# PicoPrint-MOSFETs.net
KiCad netlist of a schematic drawn in Altium Designer
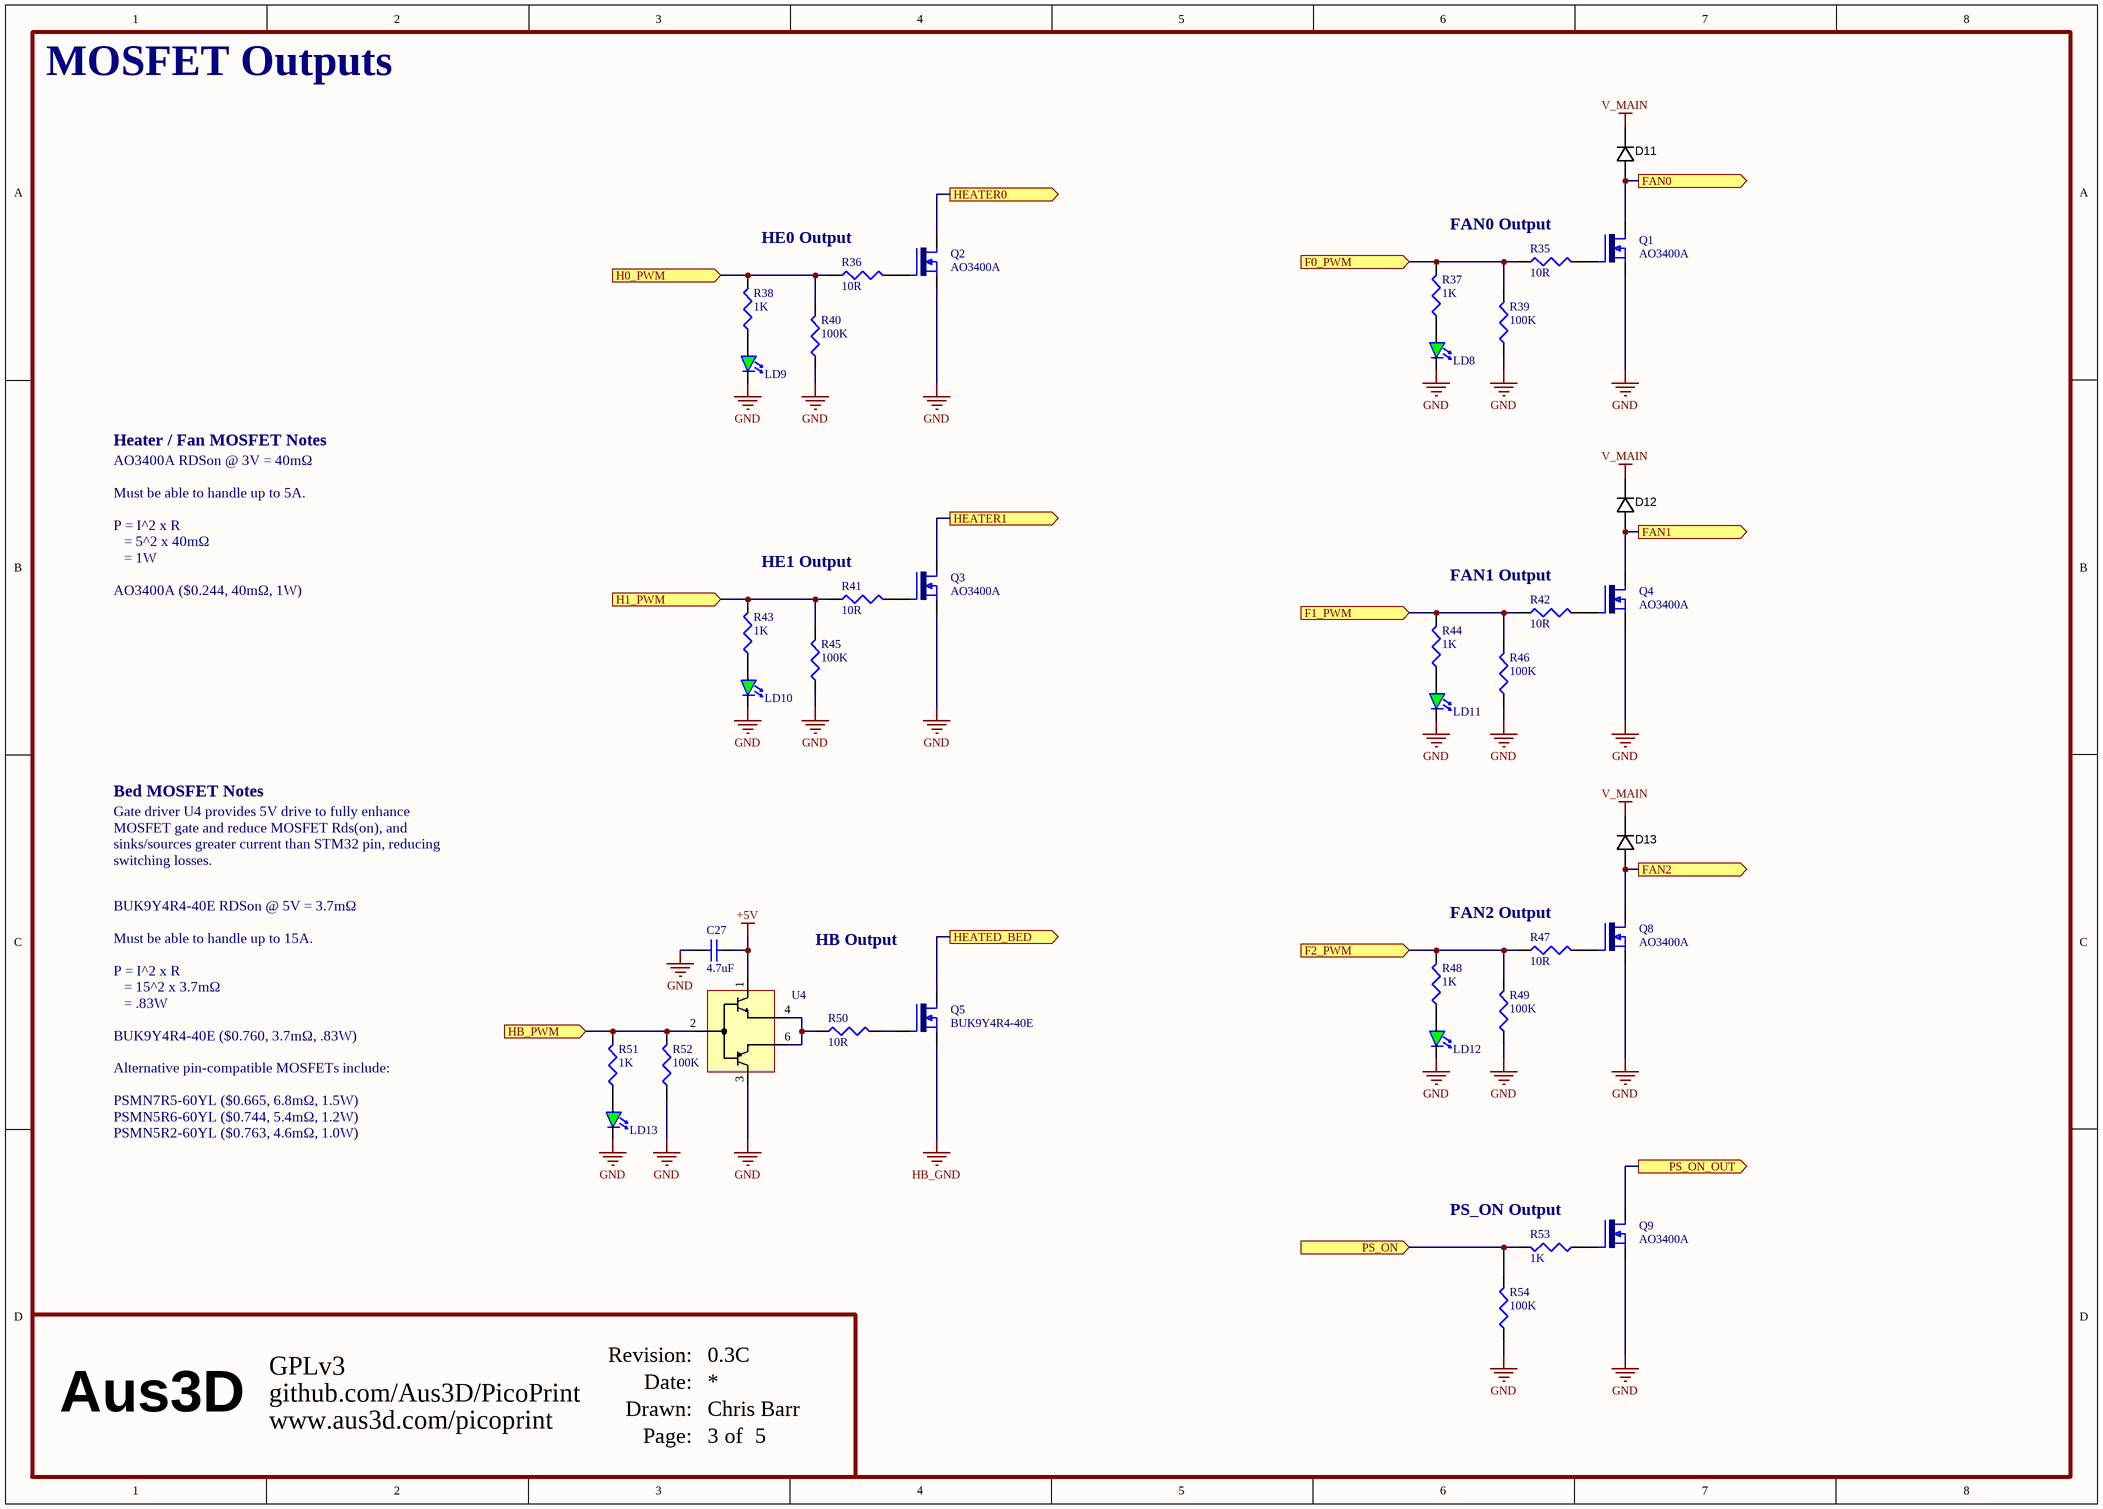
[diagram p0: PicoPrint-MOSFETs.SchDoc]

(export (version "E")
  (design (tool "Eeschema 10.0.6"))
  (components
    (comp (ref "C27")
      (value "4.7uF")
      (footprint "CAP 1005-0402")
      (description "Capacitor (SMD Ceramic)")
      (fields
        (field (name "VOLTAGE") "10V")
        (field (name "Comment") "CapC-0402-4.7uF-10V")
        (field (name "PUBLISHER") "Altium Limited")
      )
      (libsource (lib "picoprint_library") (part "CapC-0402-4.7uF-10V"))
    )
    (comp (ref "D11")
      (value "General 500mW 75V SOD323")
      (footprint "SOD323")
      (description "Diode (SMD)")
      (fields
        (field (name "MANUFACTURER") "Micro Commercial Co")
        (field (name "MANUFACTURER PART NUMBER") "1N4148WX-TP")
      )
      (libsource (lib "PBL - Diodes") (part "DIODE_75V_500mW"))
    )
    (comp (ref "D12")
      (value "General 500mW 75V SOD323")
      (footprint "SOD323")
      (description "Diode (SMD)")
      (fields
        (field (name "MANUFACTURER") "Micro Commercial Co")
        (field (name "MANUFACTURER PART NUMBER") "1N4148WX-TP")
      )
      (libsource (lib "PBL - Diodes") (part "DIODE_75V_500mW"))
    )
    (comp (ref "D13")
      (value "General 500mW 75V SOD323")
      (footprint "SOD323")
      (description "Diode (SMD)")
      (fields
        (field (name "MANUFACTURER") "Micro Commercial Co")
        (field (name "MANUFACTURER PART NUMBER") "1N4148WX-TP")
      )
      (libsource (lib "PBL - Diodes") (part "DIODE_75V_500mW"))
    )
    (comp (ref "LD8")
      (value "LED-0402")
      (footprint "LED 0402")
      (description "LED (SMD)")
      (libsource (lib "picoprint_library") (part "LEDG  0402"))
    )
    (comp (ref "LD9")
      (value "LED-0402")
      (footprint "LED 0402")
      (description "LED (SMD)")
      (libsource (lib "picoprint_library") (part "LEDG  0402"))
    )
    (comp (ref "LD10")
      (value "LED-0402")
      (footprint "LED 0402")
      (description "LED (SMD)")
      (libsource (lib "picoprint_library") (part "LEDG  0402"))
    )
    (comp (ref "LD11")
      (value "LED-0402")
      (footprint "LED 0402")
      (description "LED (SMD)")
      (libsource (lib "picoprint_library") (part "LEDG  0402"))
    )
    (comp (ref "LD12")
      (value "LED-0402")
      (footprint "LED 0402")
      (description "LED (SMD)")
      (libsource (lib "picoprint_library") (part "LEDG  0402"))
    )
    (comp (ref "LD13")
      (value "LED-0402")
      (footprint "LED 0402")
      (description "LED (SMD)")
      (libsource (lib "picoprint_library") (part "LEDG  0402"))
    )
    (comp (ref "Q1")
      (value "AO3400A")
      (footprint "SOT23-3 New")
      (description "N-CH MOSFET 30V 5.7A SOT23")
      (libsource (lib "picoprint_library") (part "MOSFET - AO3400A"))
    )
    (comp (ref "Q2")
      (value "AO3400A")
      (footprint "SOT23-3 New")
      (description "N-CH MOSFET 30V 5.7A SOT23")
      (libsource (lib "picoprint_library") (part "MOSFET - AO3400A"))
    )
    (comp (ref "Q3")
      (value "AO3400A")
      (footprint "SOT23-3 New")
      (description "N-CH MOSFET 30V 5.7A SOT23")
      (libsource (lib "picoprint_library") (part "MOSFET - AO3400A"))
    )
    (comp (ref "Q4")
      (value "AO3400A")
      (footprint "SOT23-3 New")
      (description "N-CH MOSFET 30V 5.7A SOT23")
      (libsource (lib "picoprint_library") (part "MOSFET - AO3400A"))
    )
    (comp (ref "Q5")
      (value "BUK9Y4R4-40E")
      (footprint "LFPACK")
      (description "N-CH MOSFET 40V 100A LFPAK")
      (libsource (lib "picoprint_library") (part "MOSFET - PSMN1R8-40YLC"))
    )
    (comp (ref "Q8")
      (value "AO3400A")
      (footprint "SOT23-3 New")
      (description "N-CH MOSFET 30V 5.7A SOT23")
      (libsource (lib "picoprint_library") (part "MOSFET - AO3400A"))
    )
    (comp (ref "Q9")
      (value "AO3400A")
      (footprint "SOT23-3 New")
      (description "N-CH MOSFET 30V 5.7A SOT23")
      (libsource (lib "picoprint_library") (part "MOSFET - AO3400A"))
    )
    (comp (ref "R35")
      (value "10R")
      (footprint "RESC1005X40N")
      (description "Resistor")
      (fields (field (name "Comment") "Res-0402-10R") (field (name "PUBLISHER") "Altium Limited"))
      (libsource (lib "picoprint_library") (part "Res-0402-10R"))
    )
    (comp (ref "R36")
      (value "10R")
      (footprint "RESC1005X40N")
      (description "Resistor")
      (fields (field (name "Comment") "Res-0402-10R") (field (name "PUBLISHER") "Altium Limited"))
      (libsource (lib "picoprint_library") (part "Res-0402-10R"))
    )
    (comp (ref "R37")
      (value "1K")
      (footprint "RESC1005X40N")
      (description "Resistor")
      (fields (field (name "Comment") "Res-0402-1K") (field (name "PUBLISHER") "Altium Limited"))
      (libsource (lib "picoprint_library") (part "Res-0402-1K"))
    )
    (comp (ref "R38")
      (value "1K")
      (footprint "RESC1005X40N")
      (description "Resistor")
      (fields (field (name "Comment") "Res-0402-1K") (field (name "PUBLISHER") "Altium Limited"))
      (libsource (lib "picoprint_library") (part "Res-0402-1K"))
    )
    (comp (ref "R39")
      (value "100K")
      (footprint "RESC1005X40N")
      (description "Resistor")
      (fields (field (name "Comment") "Res-0402-100K") (field (name "PUBLISHER") "Altium Limited"))
      (libsource (lib "picoprint_library") (part "Res-0402-100K"))
    )
    (comp (ref "R40")
      (value "100K")
      (footprint "RESC1005X40N")
      (description "Resistor")
      (fields (field (name "Comment") "Res-0402-100K") (field (name "PUBLISHER") "Altium Limited"))
      (libsource (lib "picoprint_library") (part "Res-0402-100K"))
    )
    (comp (ref "R41")
      (value "10R")
      (footprint "RESC1005X40N")
      (description "Resistor")
      (fields (field (name "Comment") "Res-0402-10R") (field (name "PUBLISHER") "Altium Limited"))
      (libsource (lib "picoprint_library") (part "Res-0402-10R"))
    )
    (comp (ref "R42")
      (value "10R")
      (footprint "RESC1005X40N")
      (description "Resistor")
      (fields (field (name "Comment") "Res-0402-10R") (field (name "PUBLISHER") "Altium Limited"))
      (libsource (lib "picoprint_library") (part "Res-0402-10R"))
    )
    (comp (ref "R43")
      (value "1K")
      (footprint "RESC1005X40N")
      (description "Resistor")
      (fields (field (name "Comment") "Res-0402-1K") (field (name "PUBLISHER") "Altium Limited"))
      (libsource (lib "picoprint_library") (part "Res-0402-1K"))
    )
    (comp (ref "R44")
      (value "1K")
      (footprint "RESC1005X40N")
      (description "Resistor")
      (fields (field (name "Comment") "Res-0402-1K") (field (name "PUBLISHER") "Altium Limited"))
      (libsource (lib "picoprint_library") (part "Res-0402-1K"))
    )
    (comp (ref "R45")
      (value "100K")
      (footprint "RESC1005X40N")
      (description "Resistor")
      (fields (field (name "Comment") "Res-0402-100K") (field (name "PUBLISHER") "Altium Limited"))
      (libsource (lib "picoprint_library") (part "Res-0402-100K"))
    )
    (comp (ref "R46")
      (value "100K")
      (footprint "RESC1005X40N")
      (description "Resistor")
      (fields (field (name "Comment") "Res-0402-100K") (field (name "PUBLISHER") "Altium Limited"))
      (libsource (lib "picoprint_library") (part "Res-0402-100K"))
    )
    (comp (ref "R47")
      (value "10R")
      (footprint "RESC1005X40N")
      (description "Resistor")
      (fields (field (name "Comment") "Res-0402-10R") (field (name "PUBLISHER") "Altium Limited"))
      (libsource (lib "picoprint_library") (part "Res-0402-10R"))
    )
    (comp (ref "R48")
      (value "1K")
      (footprint "RESC1005X40N")
      (description "Resistor")
      (fields (field (name "Comment") "Res-0402-1K") (field (name "PUBLISHER") "Altium Limited"))
      (libsource (lib "picoprint_library") (part "Res-0402-1K"))
    )
    (comp (ref "R49")
      (value "100K")
      (footprint "RESC1005X40N")
      (description "Resistor")
      (fields (field (name "Comment") "Res-0402-100K") (field (name "PUBLISHER") "Altium Limited"))
      (libsource (lib "picoprint_library") (part "Res-0402-100K"))
    )
    (comp (ref "R50")
      (value "10R")
      (footprint "RESC1005X40N")
      (description "Resistor")
      (fields (field (name "Comment") "Res-0402-10R") (field (name "PUBLISHER") "Altium Limited"))
      (libsource (lib "picoprint_library") (part "Res-0402-10R"))
    )
    (comp (ref "R51")
      (value "1K")
      (footprint "RESC1005X40N")
      (description "Resistor")
      (fields (field (name "Comment") "Res-0402-1K") (field (name "PUBLISHER") "Altium Limited"))
      (libsource (lib "picoprint_library") (part "Res-0402-1K"))
    )
    (comp (ref "R52")
      (value "100K")
      (footprint "RESC1005X40N")
      (description "Resistor")
      (fields (field (name "Comment") "Res-0402-100K") (field (name "PUBLISHER") "Altium Limited"))
      (libsource (lib "picoprint_library") (part "Res-0402-100K"))
    )
    (comp (ref "R53")
      (value "1K")
      (footprint "RESC1005X40N")
      (description "Resistor")
      (fields (field (name "Comment") "Res-0402-1K") (field (name "PUBLISHER") "Altium Limited"))
      (libsource (lib "picoprint_library") (part "Res-0402-1K"))
    )
    (comp (ref "R54")
      (value "100K")
      (footprint "RESC1005X40N")
      (description "Resistor")
      (fields (field (name "Comment") "Res-0402-100K") (field (name "PUBLISHER") "Altium Limited"))
      (libsource (lib "picoprint_library") (part "Res-0402-100K"))
    )
    (comp (ref "U4")
      (value "Gate Driver")
      (footprint "SOT363")
      (description "MOSFET Gate Driver IC")
      (libsource (lib "picoprint_library") (part "MOSFET Driver - 40V 1A Gate Driver ZXGD3009DY"))
    )
  )
  (nets
    (net (code "1") (name "+5V") (class "Default")
      (node (ref "C27") (pin "1") (pinfunction "1_1") (pintype "passive"))
      (node (ref "U4") (pin "1") (pinfunction "VCC_1") (pintype "passive"))
    )
    (net (code "2") (name "/F0_PWM") (class "Default")
      (node (ref "R35") (pin "1") (pinfunction "1_1") (pintype "passive"))
      (node (ref "R37") (pin "2") (pinfunction "2_2") (pintype "passive"))
      (node (ref "R39") (pin "2") (pinfunction "2_2") (pintype "passive"))
    )
    (net (code "3") (name "/F1_PWM") (class "Default")
      (node (ref "R42") (pin "1") (pinfunction "1_1") (pintype "passive"))
      (node (ref "R44") (pin "2") (pinfunction "2_2") (pintype "passive"))
      (node (ref "R46") (pin "2") (pinfunction "2_2") (pintype "passive"))
    )
    (net (code "4") (name "/F2_PWM") (class "Default")
      (node (ref "R47") (pin "1") (pinfunction "1_1") (pintype "passive"))
      (node (ref "R48") (pin "2") (pinfunction "2_2") (pintype "passive"))
      (node (ref "R49") (pin "2") (pinfunction "2_2") (pintype "passive"))
    )
    (net (code "5") (name "/FAN0") (class "Default")
      (node (ref "D11") (pin "A") (pinfunction "A_A") (pintype "passive"))
      (node (ref "Q1") (pin "3") (pinfunction "D_3") (pintype "passive"))
    )
    (net (code "6") (name "/FAN1") (class "Default")
      (node (ref "D12") (pin "A") (pinfunction "A_A") (pintype "passive"))
      (node (ref "Q4") (pin "3") (pinfunction "D_3") (pintype "passive"))
    )
    (net (code "7") (name "/FAN2") (class "Default")
      (node (ref "D13") (pin "A") (pinfunction "A_A") (pintype "passive"))
      (node (ref "Q8") (pin "3") (pinfunction "D_3") (pintype "passive"))
    )
    (net (code "8") (name "/H0_PWM") (class "Default")
      (node (ref "R36") (pin "1") (pinfunction "1_1") (pintype "passive"))
      (node (ref "R38") (pin "2") (pinfunction "2_2") (pintype "passive"))
      (node (ref "R40") (pin "2") (pinfunction "2_2") (pintype "passive"))
    )
    (net (code "9") (name "/H1_PWM") (class "Default")
      (node (ref "R41") (pin "1") (pinfunction "1_1") (pintype "passive"))
      (node (ref "R43") (pin "2") (pinfunction "2_2") (pintype "passive"))
      (node (ref "R45") (pin "2") (pinfunction "2_2") (pintype "passive"))
    )
    (net (code "10") (name "/HB_PWM") (class "Default")
      (node (ref "R51") (pin "2") (pinfunction "2_2") (pintype "passive"))
      (node (ref "R52") (pin "2") (pinfunction "2_2") (pintype "passive"))
      (node (ref "U4") (pin "2") (pinfunction "IN_2") (pintype "passive"))
    )
    (net (code "11") (name "/HEATED_BED") (class "Default")
      (node (ref "Q5") (pin "2") (pinfunction "D_2") (pintype "passive"))
    )
    (net (code "12") (name "/HEATER0") (class "Default")
      (node (ref "Q2") (pin "3") (pinfunction "D_3") (pintype "passive"))
    )
    (net (code "13") (name "/HEATER1") (class "Default")
      (node (ref "Q3") (pin "3") (pinfunction "D_3") (pintype "passive"))
    )
    (net (code "14") (name "/PS_ON") (class "Default")
      (node (ref "R53") (pin "2") (pinfunction "2_2") (pintype "passive"))
      (node (ref "R54") (pin "2") (pinfunction "2_2") (pintype "passive"))
    )
    (net (code "15") (name "/PS_ON_OUT") (class "Default")
      (node (ref "Q9") (pin "3") (pinfunction "D_3") (pintype "passive"))
    )
    (net (code "16") (name "GND") (class "Default")
      (node (ref "C27") (pin "2") (pinfunction "2_2") (pintype "passive"))
      (node (ref "LD10") (pin "2") (pinfunction "K_2") (pintype "passive"))
      (node (ref "LD11") (pin "2") (pinfunction "K_2") (pintype "passive"))
      (node (ref "LD12") (pin "2") (pinfunction "K_2") (pintype "passive"))
      (node (ref "LD13") (pin "2") (pinfunction "K_2") (pintype "passive"))
      (node (ref "LD8") (pin "2") (pinfunction "K_2") (pintype "passive"))
      (node (ref "LD9") (pin "2") (pinfunction "K_2") (pintype "passive"))
      (node (ref "Q1") (pin "2") (pinfunction "S_2") (pintype "passive"))
      (node (ref "Q2") (pin "2") (pinfunction "S_2") (pintype "passive"))
      (node (ref "Q3") (pin "2") (pinfunction "S_2") (pintype "passive"))
      (node (ref "Q4") (pin "2") (pinfunction "S_2") (pintype "passive"))
      (node (ref "Q8") (pin "2") (pinfunction "S_2") (pintype "passive"))
      (node (ref "Q9") (pin "2") (pinfunction "S_2") (pintype "passive"))
      (node (ref "R39") (pin "1") (pinfunction "1_1") (pintype "passive"))
      (node (ref "R40") (pin "1") (pinfunction "1_1") (pintype "passive"))
      (node (ref "R45") (pin "1") (pinfunction "1_1") (pintype "passive"))
      (node (ref "R46") (pin "1") (pinfunction "1_1") (pintype "passive"))
      (node (ref "R49") (pin "1") (pinfunction "1_1") (pintype "passive"))
      (node (ref "R52") (pin "1") (pinfunction "1_1") (pintype "passive"))
      (node (ref "R54") (pin "1") (pinfunction "1_1") (pintype "passive"))
      (node (ref "U4") (pin "3") (pinfunction "VEE_3") (pintype "passive"))
    )
    (net (code "17") (name "HB_GND") (class "Default")
      (node (ref "Q5") (pin "3") (pinfunction "S_3") (pintype "passive"))
    )
    (net (code "18") (name "Net-(LD8-A)") (class "Default")
      (node (ref "LD8") (pin "1") (pinfunction "A_1") (pintype "passive"))
      (node (ref "R37") (pin "1") (pinfunction "1_1") (pintype "passive"))
    )
    (net (code "19") (name "Net-(LD9-A)") (class "Default")
      (node (ref "LD9") (pin "1") (pinfunction "A_1") (pintype "passive"))
      (node (ref "R38") (pin "1") (pinfunction "1_1") (pintype "passive"))
    )
    (net (code "20") (name "Net-(LD10-A)") (class "Default")
      (node (ref "LD10") (pin "1") (pinfunction "A_1") (pintype "passive"))
      (node (ref "R43") (pin "1") (pinfunction "1_1") (pintype "passive"))
    )
    (net (code "21") (name "Net-(LD11-A)") (class "Default")
      (node (ref "LD11") (pin "1") (pinfunction "A_1") (pintype "passive"))
      (node (ref "R44") (pin "1") (pinfunction "1_1") (pintype "passive"))
    )
    (net (code "22") (name "Net-(LD12-A)") (class "Default")
      (node (ref "LD12") (pin "1") (pinfunction "A_1") (pintype "passive"))
      (node (ref "R48") (pin "1") (pinfunction "1_1") (pintype "passive"))
    )
    (net (code "23") (name "Net-(LD13-A)") (class "Default")
      (node (ref "LD13") (pin "1") (pinfunction "A_1") (pintype "passive"))
      (node (ref "R51") (pin "1") (pinfunction "1_1") (pintype "passive"))
    )
    (net (code "24") (name "Net-(Q1-G)") (class "Default")
      (node (ref "Q1") (pin "1") (pinfunction "G_1") (pintype "passive"))
      (node (ref "R35") (pin "2") (pinfunction "2_2") (pintype "passive"))
    )
    (net (code "25") (name "Net-(Q2-G)") (class "Default")
      (node (ref "Q2") (pin "1") (pinfunction "G_1") (pintype "passive"))
      (node (ref "R36") (pin "2") (pinfunction "2_2") (pintype "passive"))
    )
    (net (code "26") (name "Net-(Q3-G)") (class "Default")
      (node (ref "Q3") (pin "1") (pinfunction "G_1") (pintype "passive"))
      (node (ref "R41") (pin "2") (pinfunction "2_2") (pintype "passive"))
    )
    (net (code "27") (name "Net-(Q4-G)") (class "Default")
      (node (ref "Q4") (pin "1") (pinfunction "G_1") (pintype "passive"))
      (node (ref "R42") (pin "2") (pinfunction "2_2") (pintype "passive"))
    )
    (net (code "28") (name "Net-(Q5-G)") (class "Default")
      (node (ref "Q5") (pin "1") (pinfunction "G_1") (pintype "passive"))
      (node (ref "R50") (pin "2") (pinfunction "2_2") (pintype "passive"))
    )
    (net (code "29") (name "Net-(Q8-G)") (class "Default")
      (node (ref "Q8") (pin "1") (pinfunction "G_1") (pintype "passive"))
      (node (ref "R47") (pin "2") (pinfunction "2_2") (pintype "passive"))
    )
    (net (code "30") (name "Net-(Q9-G)") (class "Default")
      (node (ref "Q9") (pin "1") (pinfunction "G_1") (pintype "passive"))
      (node (ref "R53") (pin "1") (pinfunction "1_1") (pintype "passive"))
    )
    (net (code "31") (name "Net-(U4-SINK)") (class "Default")
      (node (ref "R50") (pin "1") (pinfunction "1_1") (pintype "passive"))
      (node (ref "U4") (pin "4") (pinfunction "SOURCE_4") (pintype "passive"))
      (node (ref "U4") (pin "6") (pinfunction "SINK_6") (pintype "passive"))
    )
    (net (code "32") (name "V_MAIN") (class "Default")
      (node (ref "D11") (pin "K") (pinfunction "K_K") (pintype "passive"))
      (node (ref "D12") (pin "K") (pinfunction "K_K") (pintype "passive"))
      (node (ref "D13") (pin "K") (pinfunction "K_K") (pintype "passive"))
    )
  )
)
